# EthernetSheet.net
KiCad netlist of a schematic drawn in Altium Designer
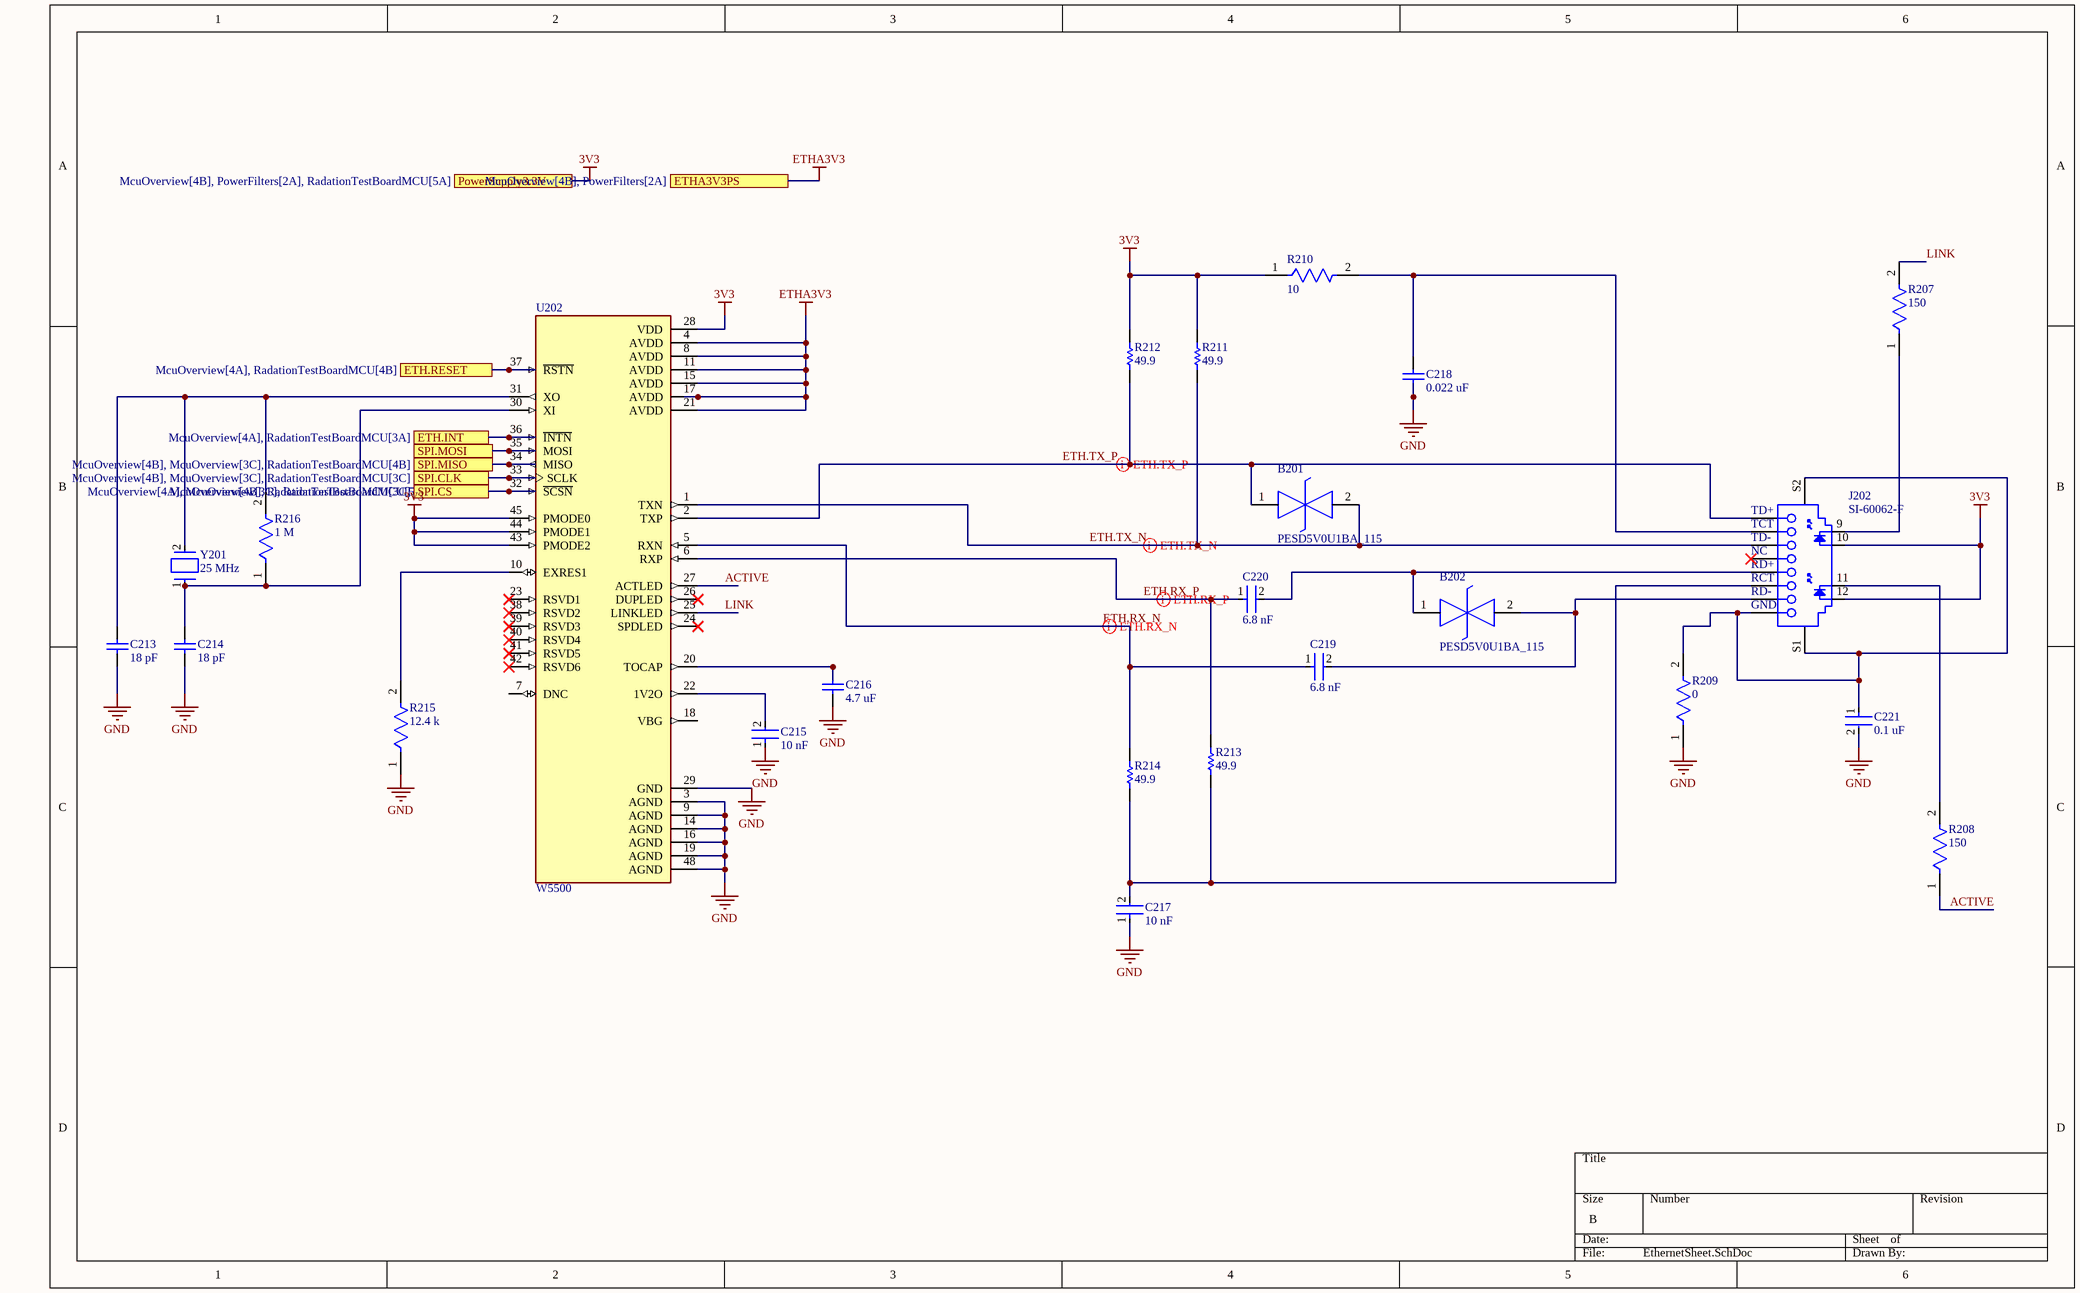
[diagram p0: EthernetSheet.SchDoc]

(export (version "E")
  (design (tool "Eeschema 10.0.6"))
  (components
    (comp (ref "B201")
      (value "PESD5V0U1BA_115")
      (footprint "PESD5V0U1BA115")
      (description "PESDV0U1BA - Low capacitance bidirectional ESD protection diode")
      (fields
        (field (name "MOUSER PART NUMBER") "771-PESD5V0U1BA115")
        (field (name "MANUFACTURER_PART_NUMBER") "PESD5V0U1BA,115")
      )
      (libsource (lib "PESD5V0U1BA_115") (part "PESD5V0U1BA_115"))
    )
    (comp (ref "B202")
      (value "PESD5V0U1BA_115")
      (footprint "PESD5V0U1BA115")
      (description "PESDV0U1BA - Low capacitance bidirectional ESD protection diode")
      (fields
        (field (name "MOUSER PART NUMBER") "771-PESD5V0U1BA115")
        (field (name "MANUFACTURER_PART_NUMBER") "PESD5V0U1BA,115")
      )
      (libsource (lib "PESD5V0U1BA_115") (part "PESD5V0U1BA_115"))
    )
    (comp (ref "C213")
      (value "18 pF")
      (footprint "CAPC1608X90X35LL15T15")
      (description "06035A180FAT2A")
      (fields (field (name "MANUFACTURER") "AVX Interconnect / Elco"))
      (libsource (lib "Altium Content Vault") (part "CAP"))
    )
    (comp (ref "C214")
      (value "18 pF")
      (footprint "CAPC1608X90X35LL15T15")
      (description "06035A180FAT2A")
      (fields (field (name "MANUFACTURER") "AVX Interconnect / Elco"))
      (libsource (lib "Altium Content Vault") (part "CAP"))
    )
    (comp (ref "C215")
      (value "10 nF")
      (footprint "FP-0603-L_1_6_0_15-W_0_81-IPC_C")
      (description "CAP CER 10000PF 50V X7R 0603 06035C103KAT4A")
      (fields (field (name "TOLERANCE") "10%") (field (name "VOLTAGE") "50V"))
      (libsource (lib "Altium Content Vault") (part "02cd4be3c70576c341d710602a673aa"))
    )
    (comp (ref "C216")
      (value "4.7 uF")
      (footprint "CAPC1608X87X35NL15T15")
      (description "C0603C475K8PACTU")
      (fields (field (name "MANUFACTURER") "Kemet"))
      (libsource (lib "Altium Content Vault") (part "CAP"))
    )
    (comp (ref "C217")
      (value "10 nF")
      (footprint "FP-0603-L_1_6_0_15-W_0_81-IPC_C")
      (description "CAP CER 10000PF 50V X7R 0603 06035C103KAT4A")
      (fields (field (name "TOLERANCE") "10%") (field (name "VOLTAGE") "50V"))
      (libsource (lib "Altium Content Vault") (part "02cd4be3c70576c341d710602a673aa"))
    )
    (comp (ref "C218")
      (value "0.022 uF")
      (footprint "CAPC1608X92X38LL15T08")
      (description "VJ0603Y223JXAAC")
      (fields (field (name "MANUFACTURER") "Vitramon"))
      (libsource (lib "Altium Content Vault") (part "CAP"))
    )
    (comp (ref "C219")
      (value "6.8 nF")
      (footprint "FP-CGA3E-0_3-0_1-IPC_A")
      (description "Cap Ceramic 6.8nF 50V C0G 5% Pad SMD 0603 +125°C Automotive T/R CGA3E2C0G1H682J080AE")
      (libsource (lib "Altium Content Vault") (part "b4654b650e69147ec39a6b967a45e02"))
    )
    (comp (ref "C220")
      (value "6.8 nF")
      (footprint "FP-CGA3E-0_3-0_1-IPC_A")
      (description "Cap Ceramic 6.8nF 50V C0G 5% Pad SMD 0603 +125°C Automotive T/R CGA3E2C0G1H682J080AE")
      (libsource (lib "Altium Content Vault") (part "b4654b650e69147ec39a6b967a45e02"))
    )
    (comp (ref "C221")
      (value "0.1 uF")
      (footprint "FP-CC0603-DA-IPC_A")
      (description "CAP CER 0.1UF 50V X7R 0603 CC0603JRX7R9BB104")
      (fields (field (name "TOLERANCE") "5%"))
      (libsource (lib "Altium Content Vault") (part "02cd4be3c70576c341d710602a673aa"))
    )
    (comp (ref "J202")
      (value "SI-60062-F")
      (footprint "BELF-SI-60062-F_V")
      (description "1 Port RJ45 Magjack Connector with Yellow and Green LED, 10/100 Base-T, 12-Pin THD, RoHS, Tray")
      (fields (field (name "MANUFACTURER") "Bel Fuse"))
      (libsource (lib "Altium Content Vault") (part "RJ45-12-2SHLD"))
    )
    (comp (ref "R207")
      (value "150")
      (footprint "FP-CRCW0603-e3-MFG")
      (description "RES Thick Film, 150Ω, 1%, 0.1W, 100ppm/°C, 0603 CRCW0603150RFKEA")
      (fields (field (name "TOLERANCE") "1%"))
      (libsource (lib "Altium Content Vault") (part "1029c3af85768c4190bb7ad29bc67b5"))
    )
    (comp (ref "R208")
      (value "150")
      (footprint "FP-CRCW0603-e3-MFG")
      (description "RES Thick Film, 150Ω, 1%, 0.1W, 100ppm/°C, 0603 CRCW0603150RFKEA")
      (fields (field (name "TOLERANCE") "1%"))
      (libsource (lib "Altium Content Vault") (part "1029c3af85768c4190bb7ad29bc67b5"))
    )
    (comp (ref "R209")
      (value "0")
      (footprint "FP-CRCW0402-e3-IPC_C")
      (description "RES Thick Film, 0Ω, 0.063W, 0402 CRCW04020000Z0ED")
      (fields (field (name "TOLERANCE") "5%"))
      (libsource (lib "Altium Content Vault") (part "1029c3af85768c4190bb7ad29bc67b5"))
    )
    (comp (ref "R210")
      (value "10")
      (footprint "FP-CRCW0603-e3-IPC_A")
      (description "RES Thick Film, 10Ω, 1%, 0.1W, 100ppm/°C, 0603 CRCW060310R0FKEA")
      (fields (field (name "TOLERANCE") "1%"))
      (libsource (lib "Altium Content Vault") (part "1029c3af85768c4190bb7ad29bc67b5"))
    )
    (comp (ref "R211")
      (value "49.9")
      (footprint "RESC1609X50X30NL10T20")
      (description "CRCW060349R9FKEC 0603 49.9 ohm Resistor")
      (fields (field (name "MANUFACTURER") "Vishay Dale") (field (name "PART NUMBER") "CRCW060349R9FKEC"))
      (libsource (lib "Altium Content Vault") (part "RES"))
    )
    (comp (ref "R212")
      (value "49.9")
      (footprint "RESC1609X50X30NL10T20")
      (description "CRCW060349R9FKEC 0603 49.9 ohm Resistor")
      (fields (field (name "MANUFACTURER") "Vishay Dale") (field (name "PART NUMBER") "CRCW060349R9FKEC"))
      (libsource (lib "Altium Content Vault") (part "RES"))
    )
    (comp (ref "R213")
      (value "49.9")
      (footprint "RESC1609X50X30NL10T20")
      (description "CRCW060349R9FKEC 0603 49.9 ohm Resistor")
      (fields (field (name "MANUFACTURER") "Vishay Dale") (field (name "PART NUMBER") "CRCW060349R9FKEC"))
      (libsource (lib "Altium Content Vault") (part "RES"))
    )
    (comp (ref "R214")
      (value "49.9")
      (footprint "RESC1609X50X30NL10T20")
      (description "CRCW060349R9FKEC 0603 49.9 ohm Resistor")
      (fields (field (name "MANUFACTURER") "Vishay Dale") (field (name "PART NUMBER") "CRCW060349R9FKEC"))
      (libsource (lib "Altium Content Vault") (part "RES"))
    )
    (comp (ref "R215")
      (value "12.4 k")
      (footprint "FP-CRCW0603-e3-IPC_B")
      (description "RES Thick Film, 12.4kΩ, 1%, 0.1W, 100ppm/°C, 0603 CRCW060312K4FKEA")
      (fields (field (name "TOLERANCE") "1%"))
      (libsource (lib "Altium Content Vault") (part "1029c3af85768c4190bb7ad29bc67b5"))
    )
    (comp (ref "R216")
      (value "1 M")
      (footprint "FP-ERJ3EK-IPC_C")
      (description "RES SMD 1M OHM 1% 1/10W 0603 ERJ-3EKF1004V")
      (fields (field (name "TOLERANCE") "1%"))
      (libsource (lib "Altium Content Vault") (part "1029c3af85768c4190bb7ad29bc67b5"))
    )
    (comp (ref "U202")
      (value "W5500")
      (footprint "QFP50P900X900X160-48N:QFP50P900X900X160-48N")
      (description "Hardwired TCP/IP embedded Ethernet controller")
      (libsource (lib "W5500") (part "W5500"))
    )
    (comp (ref "Y201")
      (value "25 MHz")
      (footprint "FP-ABM3-MFG")
      (description "Crystal 25MHz ±20ppm 18pF SMD-2 5mm x 3.2mm ABM3-25.000MHZ-B2-T")
      (fields (field (name "TOLERANCE") "20ppm"))
      (libsource (lib "Altium Content Vault") (part "c23a69dc6c9e2f18f2079038eb95dd1"))
    )
  )
  (nets
    (net (code "1") (name "/ACTIVE") (class "Default")
      (node (ref "R208") (pin "1") (pinfunction "1_1") (pintype "passive"))
      (node (ref "U202") (pin "27") (pinfunction "ACTLED_27") (pintype "output"))
    )
    (net (code "2") (name "/ETH.INT") (class "Default")
      (node (ref "U202") (pin "36") (pinfunction "~{INTN}_36") (pintype "input"))
    )
    (net (code "3") (name "/ETH.RESET") (class "Default")
      (node (ref "U202") (pin "37") (pinfunction "~{RSTN}_37") (pintype "input"))
    )
    (net (code "4") (name "/ETH.RX_N") (class "Default")
      (node (ref "C219") (pin "1") (pinfunction "1_1") (pintype "passive"))
      (node (ref "R214") (pin "2") (pinfunction "2_2") (pintype "passive"))
      (node (ref "U202") (pin "5") (pinfunction "RXN_5") (pintype "input"))
    )
    (net (code "5") (name "/ETH.RX_P") (class "Default")
      (node (ref "C220") (pin "1") (pinfunction "1_1") (pintype "passive"))
      (node (ref "R213") (pin "2") (pinfunction "2_2") (pintype "passive"))
      (node (ref "U202") (pin "6") (pinfunction "RXP_6") (pintype "input"))
    )
    (net (code "6") (name "/ETH.TX_N") (class "Default")
      (node (ref "B201") (pin "2") (pinfunction "K2_2") (pintype "passive"))
      (node (ref "J202") (pin "3") (pinfunction "TD-_3") (pintype "passive"))
      (node (ref "R211") (pin "1") (pinfunction "1_1") (pintype "passive"))
      (node (ref "U202") (pin "1") (pinfunction "TXN_1") (pintype "output"))
    )
    (net (code "7") (name "/ETH.TX_P") (class "Default")
      (node (ref "B201") (pin "1") (pinfunction "K1_1") (pintype "passive"))
      (node (ref "J202") (pin "1") (pinfunction "TD+_1") (pintype "passive"))
      (node (ref "R212") (pin "1") (pinfunction "1_1") (pintype "passive"))
      (node (ref "U202") (pin "2") (pinfunction "TXP_2") (pintype "output"))
    )
    (net (code "8") (name "/LINK") (class "Default")
      (node (ref "R207") (pin "2") (pinfunction "2_2") (pintype "passive"))
      (node (ref "U202") (pin "25") (pinfunction "LINKLED_25") (pintype "output"))
    )
    (net (code "9") (name "/SPI.CLK") (class "Default")
      (node (ref "U202") (pin "33") (pinfunction "SCLK_33") (pintype "input"))
    )
    (net (code "10") (name "/SPI.CS") (class "Default")
      (node (ref "U202") (pin "32") (pinfunction "~{SCSN}_32") (pintype "input"))
    )
    (net (code "11") (name "/SPI.MISO") (class "Default")
      (node (ref "U202") (pin "34") (pinfunction "MISO_34") (pintype "output"))
    )
    (net (code "12") (name "/SPI.MOSI") (class "Default")
      (node (ref "U202") (pin "35") (pinfunction "MOSI_35") (pintype "input"))
    )
    (net (code "13") (name "3V3") (class "Default")
      (node (ref "J202") (pin "10") (pinfunction "10_10") (pintype "passive"))
      (node (ref "J202") (pin "12") (pinfunction "12_12") (pintype "passive"))
      (node (ref "R210") (pin "1") (pinfunction "1_1") (pintype "passive"))
      (node (ref "R211") (pin "2") (pinfunction "2_2") (pintype "passive"))
      (node (ref "R212") (pin "2") (pinfunction "2_2") (pintype "passive"))
      (node (ref "U202") (pin "28") (pinfunction "VDD_28") (pintype "power_in"))
      (node (ref "U202") (pin "43") (pinfunction "PMODE2_43") (pintype "input"))
      (node (ref "U202") (pin "44") (pinfunction "PMODE1_44") (pintype "input"))
      (node (ref "U202") (pin "45") (pinfunction "PMODE0_45") (pintype "input"))
    )
    (net (code "14") (name "ETHA3V3") (class "Default")
      (node (ref "U202") (pin "11") (pinfunction "AVDD_11") (pintype "power_in"))
      (node (ref "U202") (pin "15") (pinfunction "AVDD_15") (pintype "power_in"))
      (node (ref "U202") (pin "17") (pinfunction "AVDD_17") (pintype "power_in"))
      (node (ref "U202") (pin "21") (pinfunction "AVDD_21") (pintype "power_in"))
      (node (ref "U202") (pin "4") (pinfunction "AVDD_4") (pintype "power_in"))
      (node (ref "U202") (pin "8") (pinfunction "AVDD_8") (pintype "power_in"))
    )
    (net (code "15") (name "GND") (class "Default")
      (node (ref "C213") (pin "2") (pinfunction "2_2") (pintype "passive"))
      (node (ref "C214") (pin "1") (pinfunction "1_1") (pintype "passive"))
      (node (ref "C215") (pin "1") (pinfunction "1_1") (pintype "passive"))
      (node (ref "C216") (pin "1") (pinfunction "1_1") (pintype "passive"))
      (node (ref "C217") (pin "1") (pinfunction "1_1") (pintype "passive"))
      (node (ref "C218") (pin "1") (pinfunction "1_1") (pintype "passive"))
      (node (ref "C221") (pin "2") (pinfunction "2_2") (pintype "passive"))
      (node (ref "R209") (pin "1") (pinfunction "1_1") (pintype "passive"))
      (node (ref "R215") (pin "1") (pinfunction "1_1") (pintype "passive"))
      (node (ref "U202") (pin "14") (pinfunction "AGND_14") (pintype "power_in"))
      (node (ref "U202") (pin "16") (pinfunction "AGND_16") (pintype "power_in"))
      (node (ref "U202") (pin "19") (pinfunction "AGND_19") (pintype "power_in"))
      (node (ref "U202") (pin "29") (pinfunction "GND_29") (pintype "passive"))
      (node (ref "U202") (pin "3") (pinfunction "AGND_3") (pintype "power_in"))
      (node (ref "U202") (pin "48") (pinfunction "AGND_48") (pintype "power_in"))
      (node (ref "U202") (pin "9") (pinfunction "AGND_9") (pintype "power_in"))
    )
    (net (code "16") (name "Net-(B202-K1)") (class "Default")
      (node (ref "B202") (pin "1") (pinfunction "K1_1") (pintype "passive"))
      (node (ref "C220") (pin "2") (pinfunction "2_2") (pintype "passive"))
      (node (ref "J202") (pin "5") (pinfunction "RD+_5") (pintype "passive"))
    )
    (net (code "17") (name "Net-(B202-K2)") (class "Default")
      (node (ref "B202") (pin "2") (pinfunction "K2_2") (pintype "passive"))
      (node (ref "C219") (pin "2") (pinfunction "2_2") (pintype "passive"))
      (node (ref "J202") (pin "7") (pinfunction "RD-_7") (pintype "passive"))
    )
    (net (code "18") (name "Net-(J202-GND)") (class "Default")
      (node (ref "C221") (pin "1") (pinfunction "1_1") (pintype "passive"))
      (node (ref "J202") (pin "8") (pinfunction "GND_8") (pintype "passive"))
      (node (ref "J202") (pin "S1") (pinfunction "S1_S1") (pintype "passive"))
      (node (ref "J202") (pin "S2") (pinfunction "S2_S2") (pintype "passive"))
      (node (ref "R209") (pin "2") (pinfunction "2_2") (pintype "passive"))
    )
    (net (code "19") (name "Net-(J202-Pad9)") (class "Default")
      (node (ref "J202") (pin "9") (pinfunction "9_9") (pintype "passive"))
      (node (ref "R207") (pin "1") (pinfunction "1_1") (pintype "passive"))
    )
    (net (code "20") (name "Net-(J202-Pad11)") (class "Default")
      (node (ref "J202") (pin "11") (pinfunction "11_11") (pintype "passive"))
      (node (ref "R208") (pin "2") (pinfunction "2_2") (pintype "passive"))
    )
    (net (code "21") (name "Net-(J202-RCT)") (class "Default")
      (node (ref "C217") (pin "2") (pinfunction "2_2") (pintype "passive"))
      (node (ref "J202") (pin "6") (pinfunction "RCT_6") (pintype "passive"))
      (node (ref "R213") (pin "1") (pinfunction "1_1") (pintype "passive"))
      (node (ref "R214") (pin "1") (pinfunction "1_1") (pintype "passive"))
    )
    (net (code "22") (name "Net-(J202-TCT)") (class "Default")
      (node (ref "C218") (pin "2") (pinfunction "2_2") (pintype "passive"))
      (node (ref "J202") (pin "2") (pinfunction "TCT_2") (pintype "passive"))
      (node (ref "R210") (pin "2") (pinfunction "2_2") (pintype "passive"))
    )
    (net (code "23") (name "Net-(U202-1V2O)") (class "Default")
      (node (ref "C215") (pin "2") (pinfunction "2_2") (pintype "passive"))
      (node (ref "U202") (pin "22") (pinfunction "1V2O_22") (pintype "output"))
    )
    (net (code "24") (name "Net-(U202-EXRES1)") (class "Default")
      (node (ref "R215") (pin "2") (pinfunction "2_2") (pintype "passive"))
      (node (ref "U202") (pin "10") (pinfunction "EXRES1_10") (pintype "bidirectional"))
    )
    (net (code "25") (name "Net-(U202-TOCAP)") (class "Default")
      (node (ref "C216") (pin "2") (pinfunction "2_2") (pintype "passive"))
      (node (ref "U202") (pin "20") (pinfunction "TOCAP_20") (pintype "output"))
    )
    (net (code "26") (name "Net-(U202-XI)") (class "Default")
      (node (ref "C214") (pin "2") (pinfunction "2_2") (pintype "passive"))
      (node (ref "R216") (pin "1") (pinfunction "1_1") (pintype "passive"))
      (node (ref "U202") (pin "30") (pinfunction "XI_30") (pintype "input"))
      (node (ref "Y201") (pin "1") (pinfunction "1_1") (pintype "passive"))
    )
    (net (code "27") (name "Net-(U202-XO)") (class "Default")
      (node (ref "C213") (pin "1") (pinfunction "1_1") (pintype "passive"))
      (node (ref "R216") (pin "2") (pinfunction "2_2") (pintype "passive"))
      (node (ref "U202") (pin "31") (pinfunction "XO_31") (pintype "output"))
      (node (ref "Y201") (pin "2") (pinfunction "2_2") (pintype "passive"))
    )
    (net (code "28") (name "unconnected-(J202-NC-Pad4)") (class "Default")
      (node (ref "J202") (pin "4") (pinfunction "NC_4") (pintype "passive+no_connect"))
    )
    (net (code "29") (name "unconnected-(U202-DNC-Pad7)") (class "Default")
      (node (ref "U202") (pin "7") (pinfunction "DNC_7") (pintype "bidirectional"))
    )
    (net (code "30") (name "unconnected-(U202-DUPLED-Pad26)") (class "Default")
      (node (ref "U202") (pin "26") (pinfunction "DUPLED_26") (pintype "output+no_connect"))
    )
    (net (code "31") (name "unconnected-(U202-RSVD1-Pad23)") (class "Default")
      (node (ref "U202") (pin "23") (pinfunction "RSVD1_23") (pintype "input+no_connect"))
    )
    (net (code "32") (name "unconnected-(U202-RSVD2-Pad38)") (class "Default")
      (node (ref "U202") (pin "38") (pinfunction "RSVD2_38") (pintype "input+no_connect"))
    )
    (net (code "33") (name "unconnected-(U202-RSVD3-Pad39)") (class "Default")
      (node (ref "U202") (pin "39") (pinfunction "RSVD3_39") (pintype "input+no_connect"))
    )
    (net (code "34") (name "unconnected-(U202-RSVD4-Pad40)") (class "Default")
      (node (ref "U202") (pin "40") (pinfunction "RSVD4_40") (pintype "input+no_connect"))
    )
    (net (code "35") (name "unconnected-(U202-RSVD5-Pad41)") (class "Default")
      (node (ref "U202") (pin "41") (pinfunction "RSVD5_41") (pintype "input+no_connect"))
    )
    (net (code "36") (name "unconnected-(U202-RSVD6-Pad42)") (class "Default")
      (node (ref "U202") (pin "42") (pinfunction "RSVD6_42") (pintype "input+no_connect"))
    )
    (net (code "37") (name "unconnected-(U202-SPDLED-Pad24)") (class "Default")
      (node (ref "U202") (pin "24") (pinfunction "SPDLED_24") (pintype "output+no_connect"))
    )
    (net (code "38") (name "unconnected-(U202-VBG-Pad18)") (class "Default")
      (node (ref "U202") (pin "18") (pinfunction "VBG_18") (pintype "output"))
    )
  )
)
